# SDRAM.net
KiCad netlist of a schematic drawn in Altium Designer
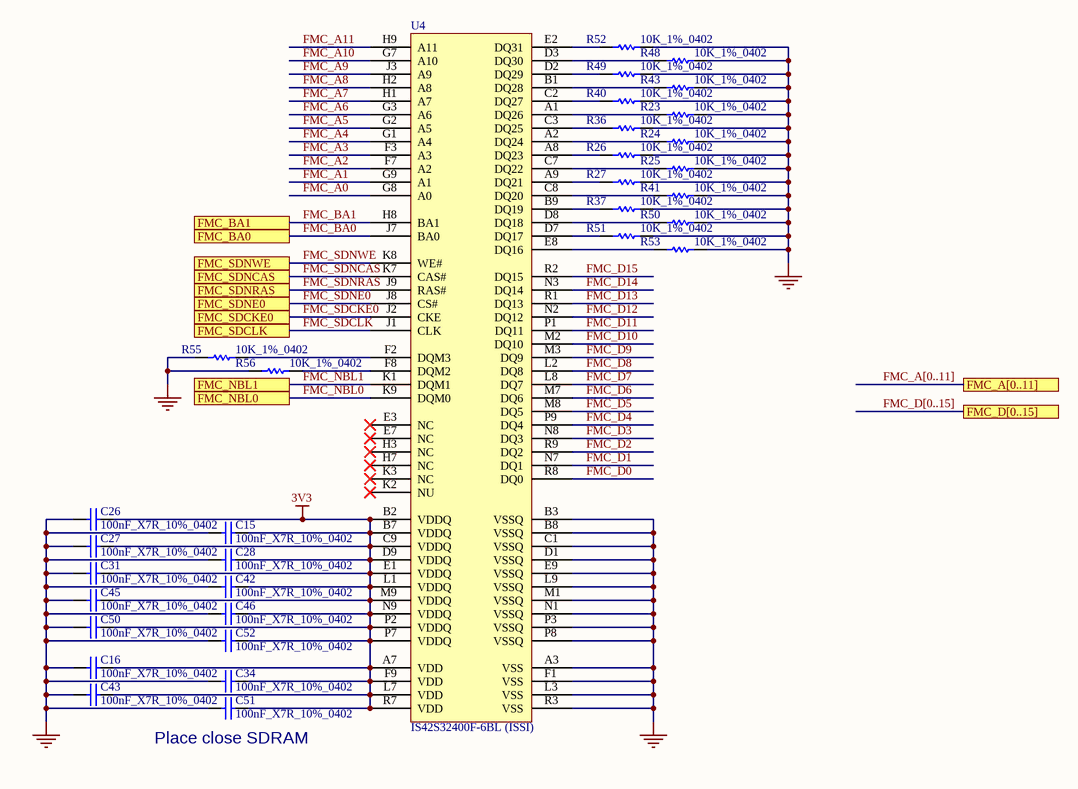
[diagram p0: SDRAM.SchDoc]

(export (version "E")
  (design (tool "Eeschema 10.0.6"))
  (components
    (comp (ref "C15")
      (value "100nF_X7R_10%_0402")
      (footprint "0402C")
      (description "Capacitor,100nF,16V,X7R,10%,0402,YAGEO")
      (libsource (lib "MCD_TOOLS") (part "Cap_100nF_X7R_10%_0402"))
    )
    (comp (ref "C16")
      (value "100nF_X7R_10%_0402")
      (footprint "0402C")
      (description "Capacitor,100nF,16V,X7R,10%,0402,YAGEO")
      (libsource (lib "MCD_TOOLS") (part "Cap_100nF_X7R_10%_0402"))
    )
    (comp (ref "C26")
      (value "100nF_X7R_10%_0402")
      (footprint "0402C")
      (description "Capacitor,100nF,16V,X7R,10%,0402,YAGEO")
      (libsource (lib "MCD_TOOLS") (part "Cap_100nF_X7R_10%_0402"))
    )
    (comp (ref "C27")
      (value "100nF_X7R_10%_0402")
      (footprint "0402C")
      (description "Capacitor,100nF,16V,X7R,10%,0402,YAGEO")
      (libsource (lib "MCD_TOOLS") (part "Cap_100nF_X7R_10%_0402"))
    )
    (comp (ref "C28")
      (value "100nF_X7R_10%_0402")
      (footprint "0402C")
      (description "Capacitor,100nF,16V,X7R,10%,0402,YAGEO")
      (libsource (lib "MCD_TOOLS") (part "Cap_100nF_X7R_10%_0402"))
    )
    (comp (ref "C31")
      (value "100nF_X7R_10%_0402")
      (footprint "0402C")
      (description "Capacitor,100nF,16V,X7R,10%,0402,YAGEO")
      (libsource (lib "MCD_TOOLS") (part "Cap_100nF_X7R_10%_0402"))
    )
    (comp (ref "C34")
      (value "100nF_X7R_10%_0402")
      (footprint "0402C")
      (description "Capacitor,100nF,16V,X7R,10%,0402,YAGEO")
      (libsource (lib "MCD_TOOLS") (part "Cap_100nF_X7R_10%_0402"))
    )
    (comp (ref "C42")
      (value "100nF_X7R_10%_0402")
      (footprint "0402C")
      (description "Capacitor,100nF,16V,X7R,10%,0402,YAGEO")
      (libsource (lib "MCD_TOOLS") (part "Cap_100nF_X7R_10%_0402"))
    )
    (comp (ref "C43")
      (value "100nF_X7R_10%_0402")
      (footprint "0402C")
      (description "Capacitor,100nF,16V,X7R,10%,0402,YAGEO")
      (libsource (lib "MCD_TOOLS") (part "Cap_100nF_X7R_10%_0402"))
    )
    (comp (ref "C45")
      (value "100nF_X7R_10%_0402")
      (footprint "0402C")
      (description "Capacitor,100nF,16V,X7R,10%,0402,YAGEO")
      (libsource (lib "MCD_TOOLS") (part "Cap_100nF_X7R_10%_0402"))
    )
    (comp (ref "C46")
      (value "100nF_X7R_10%_0402")
      (footprint "0402C")
      (description "Capacitor,100nF,16V,X7R,10%,0402,YAGEO")
      (libsource (lib "MCD_TOOLS") (part "Cap_100nF_X7R_10%_0402"))
    )
    (comp (ref "C50")
      (value "100nF_X7R_10%_0402")
      (footprint "0402C")
      (description "Capacitor,100nF,16V,X7R,10%,0402,YAGEO")
      (libsource (lib "MCD_TOOLS") (part "Cap_100nF_X7R_10%_0402"))
    )
    (comp (ref "C51")
      (value "100nF_X7R_10%_0402")
      (footprint "0402C")
      (description "Capacitor,100nF,16V,X7R,10%,0402,YAGEO")
      (libsource (lib "MCD_TOOLS") (part "Cap_100nF_X7R_10%_0402"))
    )
    (comp (ref "C52")
      (value "100nF_X7R_10%_0402")
      (footprint "0402C")
      (description "Capacitor,100nF,16V,X7R,10%,0402,YAGEO")
      (libsource (lib "MCD_TOOLS") (part "Cap_100nF_X7R_10%_0402"))
    )
    (comp (ref "R23")
      (value "10K_1%_0402")
      (footprint "0402R")
      (description "Resistor,10K,0402,1%,YAGEO")
      (libsource (lib "MCD_TOOLS") (part "Res_10K_1%_0402"))
    )
    (comp (ref "R24")
      (value "10K_1%_0402")
      (footprint "0402R")
      (description "Resistor,10K,0402,1%,YAGEO")
      (libsource (lib "MCD_TOOLS") (part "Res_10K_1%_0402"))
    )
    (comp (ref "R25")
      (value "10K_1%_0402")
      (footprint "0402R")
      (description "Resistor,10K,0402,1%,YAGEO")
      (libsource (lib "MCD_TOOLS") (part "Res_10K_1%_0402"))
    )
    (comp (ref "R26")
      (value "10K_1%_0402")
      (footprint "0402R")
      (description "Resistor,10K,0402,1%,YAGEO")
      (libsource (lib "MCD_TOOLS") (part "Res_10K_1%_0402"))
    )
    (comp (ref "R27")
      (value "10K_1%_0402")
      (footprint "0402R")
      (description "Resistor,10K,0402,1%,YAGEO")
      (libsource (lib "MCD_TOOLS") (part "Res_10K_1%_0402"))
    )
    (comp (ref "R36")
      (value "10K_1%_0402")
      (footprint "0402R")
      (description "Resistor,10K,0402,1%,YAGEO")
      (libsource (lib "MCD_TOOLS") (part "Res_10K_1%_0402"))
    )
    (comp (ref "R37")
      (value "10K_1%_0402")
      (footprint "0402R")
      (description "Resistor,10K,0402,1%,YAGEO")
      (libsource (lib "MCD_TOOLS") (part "Res_10K_1%_0402"))
    )
    (comp (ref "R40")
      (value "10K_1%_0402")
      (footprint "0402R")
      (description "Resistor,10K,0402,1%,YAGEO")
      (libsource (lib "MCD_TOOLS") (part "Res_10K_1%_0402"))
    )
    (comp (ref "R41")
      (value "10K_1%_0402")
      (footprint "0402R")
      (description "Resistor,10K,0402,1%,YAGEO")
      (libsource (lib "MCD_TOOLS") (part "Res_10K_1%_0402"))
    )
    (comp (ref "R43")
      (value "10K_1%_0402")
      (footprint "0402R")
      (description "Resistor,10K,0402,1%,YAGEO")
      (libsource (lib "MCD_TOOLS") (part "Res_10K_1%_0402"))
    )
    (comp (ref "R48")
      (value "10K_1%_0402")
      (footprint "0402R")
      (description "Resistor,10K,0402,1%,YAGEO")
      (libsource (lib "MCD_TOOLS") (part "Res_10K_1%_0402"))
    )
    (comp (ref "R49")
      (value "10K_1%_0402")
      (footprint "0402R")
      (description "Resistor,10K,0402,1%,YAGEO")
      (libsource (lib "MCD_TOOLS") (part "Res_10K_1%_0402"))
    )
    (comp (ref "R50")
      (value "10K_1%_0402")
      (footprint "0402R")
      (description "Resistor,10K,0402,1%,YAGEO")
      (libsource (lib "MCD_TOOLS") (part "Res_10K_1%_0402"))
    )
    (comp (ref "R51")
      (value "10K_1%_0402")
      (footprint "0402R")
      (description "Resistor,10K,0402,1%,YAGEO")
      (libsource (lib "MCD_TOOLS") (part "Res_10K_1%_0402"))
    )
    (comp (ref "R52")
      (value "10K_1%_0402")
      (footprint "0402R")
      (description "Resistor,10K,0402,1%,YAGEO")
      (libsource (lib "MCD_TOOLS") (part "Res_10K_1%_0402"))
    )
    (comp (ref "R53")
      (value "10K_1%_0402")
      (footprint "0402R")
      (description "Resistor,10K,0402,1%,YAGEO")
      (libsource (lib "MCD_TOOLS") (part "Res_10K_1%_0402"))
    )
    (comp (ref "R55")
      (value "10K_1%_0402")
      (footprint "0402R")
      (description "Resistor,10K,0402,1%,YAGEO")
      (libsource (lib "MCD_TOOLS") (part "Res_10K_1%_0402"))
    )
    (comp (ref "R56")
      (value "10K_1%_0402")
      (footprint "0402R")
      (description "Resistor,10K,0402,1%,YAGEO")
      (libsource (lib "MCD_TOOLS") (part "Res_10K_1%_0402"))
    )
    (comp (ref "U4")
      (value "IS42S32400F-6BL (ISSI)")
      (footprint "FBGA90_0R8_8X13")
      (description "SDRAM 128MBIT (4M x 32) 166MHZ 90-VFBGA (8x13)")
      (fields (field (name "PROVIDED") "SUBCO"))
      (libsource (lib "MCD_TOOLS") (part "MT48LC4M32B2B5-6A"))
    )
  )
  (nets
    (net (code "1") (name "/FMC_A0") (class "Default")
      (node (ref "U4") (pin "G8") (pinfunction "A0_G8") (pintype "passive"))
    )
    (net (code "2") (name "/FMC_A1") (class "Default")
      (node (ref "U4") (pin "G9") (pinfunction "A1_G9") (pintype "passive"))
    )
    (net (code "3") (name "/FMC_A2") (class "Default")
      (node (ref "U4") (pin "F7") (pinfunction "A2_F7") (pintype "passive"))
    )
    (net (code "4") (name "/FMC_A3") (class "Default")
      (node (ref "U4") (pin "F3") (pinfunction "A3_F3") (pintype "passive"))
    )
    (net (code "5") (name "/FMC_A4") (class "Default")
      (node (ref "U4") (pin "G1") (pinfunction "A4_G1") (pintype "passive"))
    )
    (net (code "6") (name "/FMC_A5") (class "Default")
      (node (ref "U4") (pin "G2") (pinfunction "A5_G2") (pintype "passive"))
    )
    (net (code "7") (name "/FMC_A6") (class "Default")
      (node (ref "U4") (pin "G3") (pinfunction "A6_G3") (pintype "passive"))
    )
    (net (code "8") (name "/FMC_A7") (class "Default")
      (node (ref "U4") (pin "H1") (pinfunction "A7_H1") (pintype "passive"))
    )
    (net (code "9") (name "/FMC_A8") (class "Default")
      (node (ref "U4") (pin "H2") (pinfunction "A8_H2") (pintype "passive"))
    )
    (net (code "10") (name "/FMC_A9") (class "Default")
      (node (ref "U4") (pin "J3") (pinfunction "A9_J3") (pintype "passive"))
    )
    (net (code "11") (name "/FMC_A10") (class "Default")
      (node (ref "U4") (pin "G7") (pinfunction "A10_G7") (pintype "passive"))
    )
    (net (code "12") (name "/FMC_A11") (class "Default")
      (node (ref "U4") (pin "H9") (pinfunction "A11_H9") (pintype "passive"))
    )
    (net (code "14") (name "/FMC_BA0") (class "Default")
      (node (ref "U4") (pin "J7") (pinfunction "BA0_J7") (pintype "passive"))
    )
    (net (code "15") (name "/FMC_BA1") (class "Default")
      (node (ref "U4") (pin "H8") (pinfunction "BA1_H8") (pintype "passive"))
    )
    (net (code "16") (name "/FMC_D0") (class "Default")
      (node (ref "U4") (pin "R8") (pinfunction "DQ0_R8") (pintype "passive"))
    )
    (net (code "17") (name "/FMC_D1") (class "Default")
      (node (ref "U4") (pin "N7") (pinfunction "DQ1_N7") (pintype "passive"))
    )
    (net (code "18") (name "/FMC_D2") (class "Default")
      (node (ref "U4") (pin "R9") (pinfunction "DQ2_R9") (pintype "passive"))
    )
    (net (code "19") (name "/FMC_D3") (class "Default")
      (node (ref "U4") (pin "N8") (pinfunction "DQ3_N8") (pintype "passive"))
    )
    (net (code "20") (name "/FMC_D4") (class "Default")
      (node (ref "U4") (pin "P9") (pinfunction "DQ4_P9") (pintype "passive"))
    )
    (net (code "21") (name "/FMC_D5") (class "Default")
      (node (ref "U4") (pin "M8") (pinfunction "DQ5_M8") (pintype "passive"))
    )
    (net (code "22") (name "/FMC_D6") (class "Default")
      (node (ref "U4") (pin "M7") (pinfunction "DQ6_M7") (pintype "passive"))
    )
    (net (code "23") (name "/FMC_D7") (class "Default")
      (node (ref "U4") (pin "L8") (pinfunction "DQ7_L8") (pintype "passive"))
    )
    (net (code "24") (name "/FMC_D8") (class "Default")
      (node (ref "U4") (pin "L2") (pinfunction "DQ8_L2") (pintype "passive"))
    )
    (net (code "25") (name "/FMC_D9") (class "Default")
      (node (ref "U4") (pin "M3") (pinfunction "DQ9_M3") (pintype "passive"))
    )
    (net (code "26") (name "/FMC_D10") (class "Default")
      (node (ref "U4") (pin "M2") (pinfunction "DQ10_M2") (pintype "passive"))
    )
    (net (code "27") (name "/FMC_D11") (class "Default")
      (node (ref "U4") (pin "P1") (pinfunction "DQ11_P1") (pintype "passive"))
    )
    (net (code "28") (name "/FMC_D12") (class "Default")
      (node (ref "U4") (pin "N2") (pinfunction "DQ12_N2") (pintype "passive"))
    )
    (net (code "29") (name "/FMC_D13") (class "Default")
      (node (ref "U4") (pin "R1") (pinfunction "DQ13_R1") (pintype "passive"))
    )
    (net (code "30") (name "/FMC_D14") (class "Default")
      (node (ref "U4") (pin "N3") (pinfunction "DQ14_N3") (pintype "passive"))
    )
    (net (code "31") (name "/FMC_D15") (class "Default")
      (node (ref "U4") (pin "R2") (pinfunction "DQ15_R2") (pintype "passive"))
    )
    (net (code "33") (name "/FMC_NBL0") (class "Default")
      (node (ref "U4") (pin "K9") (pinfunction "DQM0_K9") (pintype "passive"))
    )
    (net (code "34") (name "/FMC_NBL1") (class "Default")
      (node (ref "U4") (pin "K1") (pinfunction "DQM1_K1") (pintype "passive"))
    )
    (net (code "35") (name "/FMC_SDCKE0") (class "Default")
      (node (ref "U4") (pin "J2") (pinfunction "CKE_J2") (pintype "passive"))
    )
    (net (code "36") (name "/FMC_SDCLK") (class "Default")
      (node (ref "U4") (pin "J1") (pinfunction "CLK_J1") (pintype "passive"))
    )
    (net (code "37") (name "/FMC_SDNCAS") (class "Default")
      (node (ref "U4") (pin "K7") (pinfunction "CAS#_K7") (pintype "passive"))
    )
    (net (code "38") (name "/FMC_SDNE0") (class "Default")
      (node (ref "U4") (pin "J8") (pinfunction "CS#_J8") (pintype "passive"))
    )
    (net (code "39") (name "/FMC_SDNRAS") (class "Default")
      (node (ref "U4") (pin "J9") (pinfunction "RAS#_J9") (pintype "passive"))
    )
    (net (code "40") (name "/FMC_SDNWE") (class "Default")
      (node (ref "U4") (pin "K8") (pinfunction "WE#_K8") (pintype "passive"))
    )
    (net (code "41") (name "3V3") (class "Default")
      (node (ref "C15") (pin "2") (pinfunction "2_2") (pintype "passive"))
      (node (ref "C16") (pin "2") (pinfunction "2_2") (pintype "passive"))
      (node (ref "C26") (pin "2") (pinfunction "2_2") (pintype "passive"))
      (node (ref "C27") (pin "2") (pinfunction "2_2") (pintype "passive"))
      (node (ref "C28") (pin "2") (pinfunction "2_2") (pintype "passive"))
      (node (ref "C31") (pin "2") (pinfunction "2_2") (pintype "passive"))
      (node (ref "C34") (pin "2") (pinfunction "2_2") (pintype "passive"))
      (node (ref "C42") (pin "2") (pinfunction "2_2") (pintype "passive"))
      (node (ref "C43") (pin "2") (pinfunction "2_2") (pintype "passive"))
      (node (ref "C45") (pin "2") (pinfunction "2_2") (pintype "passive"))
      (node (ref "C46") (pin "2") (pinfunction "2_2") (pintype "passive"))
      (node (ref "C50") (pin "2") (pinfunction "2_2") (pintype "passive"))
      (node (ref "C51") (pin "2") (pinfunction "2_2") (pintype "passive"))
      (node (ref "C52") (pin "2") (pinfunction "2_2") (pintype "passive"))
      (node (ref "U4") (pin "A7") (pinfunction "VDD_A7") (pintype "passive"))
      (node (ref "U4") (pin "B2") (pinfunction "VDDQ_B2") (pintype "passive"))
      (node (ref "U4") (pin "B7") (pinfunction "VDDQ_B7") (pintype "passive"))
      (node (ref "U4") (pin "C9") (pinfunction "VDDQ_C9") (pintype "passive"))
      (node (ref "U4") (pin "D9") (pinfunction "VDDQ_D9") (pintype "passive"))
      (node (ref "U4") (pin "E1") (pinfunction "VDDQ_E1") (pintype "passive"))
      (node (ref "U4") (pin "F9") (pinfunction "VDD_F9") (pintype "passive"))
      (node (ref "U4") (pin "L1") (pinfunction "VDDQ_L1") (pintype "passive"))
      (node (ref "U4") (pin "L7") (pinfunction "VDD_L7") (pintype "passive"))
      (node (ref "U4") (pin "M9") (pinfunction "VDDQ_M9") (pintype "passive"))
      (node (ref "U4") (pin "N9") (pinfunction "VDDQ_N9") (pintype "passive"))
      (node (ref "U4") (pin "P2") (pinfunction "VDDQ_P2") (pintype "passive"))
      (node (ref "U4") (pin "P7") (pinfunction "VDDQ_P7") (pintype "passive"))
      (node (ref "U4") (pin "R7") (pinfunction "VDD_R7") (pintype "passive"))
    )
    (net (code "42") (name "GND") (class "Default")
      (node (ref "C15") (pin "1") (pinfunction "1_1") (pintype "passive"))
      (node (ref "C16") (pin "1") (pinfunction "1_1") (pintype "passive"))
      (node (ref "C26") (pin "1") (pinfunction "1_1") (pintype "passive"))
      (node (ref "C27") (pin "1") (pinfunction "1_1") (pintype "passive"))
      (node (ref "C28") (pin "1") (pinfunction "1_1") (pintype "passive"))
      (node (ref "C31") (pin "1") (pinfunction "1_1") (pintype "passive"))
      (node (ref "C34") (pin "1") (pinfunction "1_1") (pintype "passive"))
      (node (ref "C42") (pin "1") (pinfunction "1_1") (pintype "passive"))
      (node (ref "C43") (pin "1") (pinfunction "1_1") (pintype "passive"))
      (node (ref "C45") (pin "1") (pinfunction "1_1") (pintype "passive"))
      (node (ref "C46") (pin "1") (pinfunction "1_1") (pintype "passive"))
      (node (ref "C50") (pin "1") (pinfunction "1_1") (pintype "passive"))
      (node (ref "C51") (pin "1") (pinfunction "1_1") (pintype "passive"))
      (node (ref "C52") (pin "1") (pinfunction "1_1") (pintype "passive"))
      (node (ref "R23") (pin "2") (pinfunction "2_2") (pintype "passive"))
      (node (ref "R24") (pin "2") (pinfunction "2_2") (pintype "passive"))
      (node (ref "R25") (pin "2") (pinfunction "2_2") (pintype "passive"))
      (node (ref "R26") (pin "2") (pinfunction "2_2") (pintype "passive"))
      (node (ref "R27") (pin "2") (pinfunction "2_2") (pintype "passive"))
      (node (ref "R36") (pin "2") (pinfunction "2_2") (pintype "passive"))
      (node (ref "R37") (pin "2") (pinfunction "2_2") (pintype "passive"))
      (node (ref "R40") (pin "2") (pinfunction "2_2") (pintype "passive"))
      (node (ref "R41") (pin "2") (pinfunction "2_2") (pintype "passive"))
      (node (ref "R43") (pin "2") (pinfunction "2_2") (pintype "passive"))
      (node (ref "R48") (pin "2") (pinfunction "2_2") (pintype "passive"))
      (node (ref "R49") (pin "2") (pinfunction "2_2") (pintype "passive"))
      (node (ref "R50") (pin "2") (pinfunction "2_2") (pintype "passive"))
      (node (ref "R51") (pin "2") (pinfunction "2_2") (pintype "passive"))
      (node (ref "R52") (pin "2") (pinfunction "2_2") (pintype "passive"))
      (node (ref "R53") (pin "2") (pinfunction "2_2") (pintype "passive"))
      (node (ref "R55") (pin "1") (pinfunction "1_1") (pintype "passive"))
      (node (ref "R56") (pin "1") (pinfunction "1_1") (pintype "passive"))
      (node (ref "U4") (pin "A3") (pinfunction "VSS_A3") (pintype "passive"))
      (node (ref "U4") (pin "B3") (pinfunction "VSSQ_B3") (pintype "passive"))
      (node (ref "U4") (pin "B8") (pinfunction "VSSQ_B8") (pintype "passive"))
      (node (ref "U4") (pin "C1") (pinfunction "VSSQ_C1") (pintype "passive"))
      (node (ref "U4") (pin "D1") (pinfunction "VSSQ_D1") (pintype "passive"))
      (node (ref "U4") (pin "E9") (pinfunction "VSSQ_E9") (pintype "passive"))
      (node (ref "U4") (pin "F1") (pinfunction "VSS_F1") (pintype "passive"))
      (node (ref "U4") (pin "L3") (pinfunction "VSS_L3") (pintype "passive"))
      (node (ref "U4") (pin "L9") (pinfunction "VSSQ_L9") (pintype "passive"))
      (node (ref "U4") (pin "M1") (pinfunction "VSSQ_M1") (pintype "passive"))
      (node (ref "U4") (pin "N1") (pinfunction "VSSQ_N1") (pintype "passive"))
      (node (ref "U4") (pin "P3") (pinfunction "VSSQ_P3") (pintype "passive"))
      (node (ref "U4") (pin "P8") (pinfunction "VSSQ_P8") (pintype "passive"))
      (node (ref "U4") (pin "R3") (pinfunction "VSS_R3") (pintype "passive"))
    )
    (net (code "43") (name "Net-(U4-DQ16)") (class "Default")
      (node (ref "R53") (pin "1") (pinfunction "1_1") (pintype "passive"))
      (node (ref "U4") (pin "E8") (pinfunction "DQ16_E8") (pintype "passive"))
    )
    (net (code "44") (name "Net-(U4-DQ17)") (class "Default")
      (node (ref "R51") (pin "1") (pinfunction "1_1") (pintype "passive"))
      (node (ref "U4") (pin "D7") (pinfunction "DQ17_D7") (pintype "passive"))
    )
    (net (code "45") (name "Net-(U4-DQ18)") (class "Default")
      (node (ref "R50") (pin "1") (pinfunction "1_1") (pintype "passive"))
      (node (ref "U4") (pin "D8") (pinfunction "DQ18_D8") (pintype "passive"))
    )
    (net (code "46") (name "Net-(U4-DQ19)") (class "Default")
      (node (ref "R37") (pin "1") (pinfunction "1_1") (pintype "passive"))
      (node (ref "U4") (pin "B9") (pinfunction "DQ19_B9") (pintype "passive"))
    )
    (net (code "47") (name "Net-(U4-DQ20)") (class "Default")
      (node (ref "R41") (pin "1") (pinfunction "1_1") (pintype "passive"))
      (node (ref "U4") (pin "C8") (pinfunction "DQ20_C8") (pintype "passive"))
    )
    (net (code "48") (name "Net-(U4-DQ21)") (class "Default")
      (node (ref "R27") (pin "1") (pinfunction "1_1") (pintype "passive"))
      (node (ref "U4") (pin "A9") (pinfunction "DQ21_A9") (pintype "passive"))
    )
    (net (code "49") (name "Net-(U4-DQ22)") (class "Default")
      (node (ref "R25") (pin "1") (pinfunction "1_1") (pintype "passive"))
      (node (ref "U4") (pin "C7") (pinfunction "DQ22_C7") (pintype "passive"))
    )
    (net (code "50") (name "Net-(U4-DQ23)") (class "Default")
      (node (ref "R26") (pin "1") (pinfunction "1_1") (pintype "passive"))
      (node (ref "U4") (pin "A8") (pinfunction "DQ23_A8") (pintype "passive"))
    )
    (net (code "51") (name "Net-(U4-DQ24)") (class "Default")
      (node (ref "R24") (pin "1") (pinfunction "1_1") (pintype "passive"))
      (node (ref "U4") (pin "A2") (pinfunction "DQ24_A2") (pintype "passive"))
    )
    (net (code "52") (name "Net-(U4-DQ25)") (class "Default")
      (node (ref "R36") (pin "1") (pinfunction "1_1") (pintype "passive"))
      (node (ref "U4") (pin "C3") (pinfunction "DQ25_C3") (pintype "passive"))
    )
    (net (code "53") (name "Net-(U4-DQ26)") (class "Default")
      (node (ref "R23") (pin "1") (pinfunction "1_1") (pintype "passive"))
      (node (ref "U4") (pin "A1") (pinfunction "DQ26_A1") (pintype "passive"))
    )
    (net (code "54") (name "Net-(U4-DQ27)") (class "Default")
      (node (ref "R40") (pin "1") (pinfunction "1_1") (pintype "passive"))
      (node (ref "U4") (pin "C2") (pinfunction "DQ27_C2") (pintype "passive"))
    )
    (net (code "55") (name "Net-(U4-DQ28)") (class "Default")
      (node (ref "R43") (pin "1") (pinfunction "1_1") (pintype "passive"))
      (node (ref "U4") (pin "B1") (pinfunction "DQ28_B1") (pintype "passive"))
    )
    (net (code "56") (name "Net-(U4-DQ29)") (class "Default")
      (node (ref "R49") (pin "1") (pinfunction "1_1") (pintype "passive"))
      (node (ref "U4") (pin "D2") (pinfunction "DQ29_D2") (pintype "passive"))
    )
    (net (code "57") (name "Net-(U4-DQ30)") (class "Default")
      (node (ref "R48") (pin "1") (pinfunction "1_1") (pintype "passive"))
      (node (ref "U4") (pin "D3") (pinfunction "DQ30_D3") (pintype "passive"))
    )
    (net (code "58") (name "Net-(U4-DQ31)") (class "Default")
      (node (ref "R52") (pin "1") (pinfunction "1_1") (pintype "passive"))
      (node (ref "U4") (pin "E2") (pinfunction "DQ31_E2") (pintype "passive"))
    )
    (net (code "59") (name "Net-(U4-DQM2)") (class "Default")
      (node (ref "R56") (pin "2") (pinfunction "2_2") (pintype "passive"))
      (node (ref "U4") (pin "F8") (pinfunction "DQM2_F8") (pintype "passive"))
    )
    (net (code "60") (name "Net-(U4-DQM3)") (class "Default")
      (node (ref "R55") (pin "2") (pinfunction "2_2") (pintype "passive"))
      (node (ref "U4") (pin "F2") (pinfunction "DQM3_F2") (pintype "passive"))
    )
    (net (code "61") (name "unconnected-(U4-NC-PadE3)") (class "Default")
      (node (ref "U4") (pin "E3") (pinfunction "NC_E3") (pintype "passive+no_connect"))
    )
    (net (code "62") (name "unconnected-(U4-NC-PadE7)") (class "Default")
      (node (ref "U4") (pin "E7") (pinfunction "NC_E7") (pintype "passive+no_connect"))
    )
    (net (code "63") (name "unconnected-(U4-NC-PadH3)") (class "Default")
      (node (ref "U4") (pin "H3") (pinfunction "NC_H3") (pintype "passive+no_connect"))
    )
    (net (code "64") (name "unconnected-(U4-NC-PadH7)") (class "Default")
      (node (ref "U4") (pin "H7") (pinfunction "NC_H7") (pintype "passive+no_connect"))
    )
    (net (code "65") (name "unconnected-(U4-NC-PadK3)") (class "Default")
      (node (ref "U4") (pin "K3") (pinfunction "NC_K3") (pintype "passive+no_connect"))
    )
    (net (code "66") (name "unconnected-(U4-NU-PadK2)") (class "Default")
      (node (ref "U4") (pin "K2") (pinfunction "NU_K2") (pintype "passive+no_connect"))
    )
  )
)
